# aa.net
KiCad netlist of a schematic drawn in EAGLE
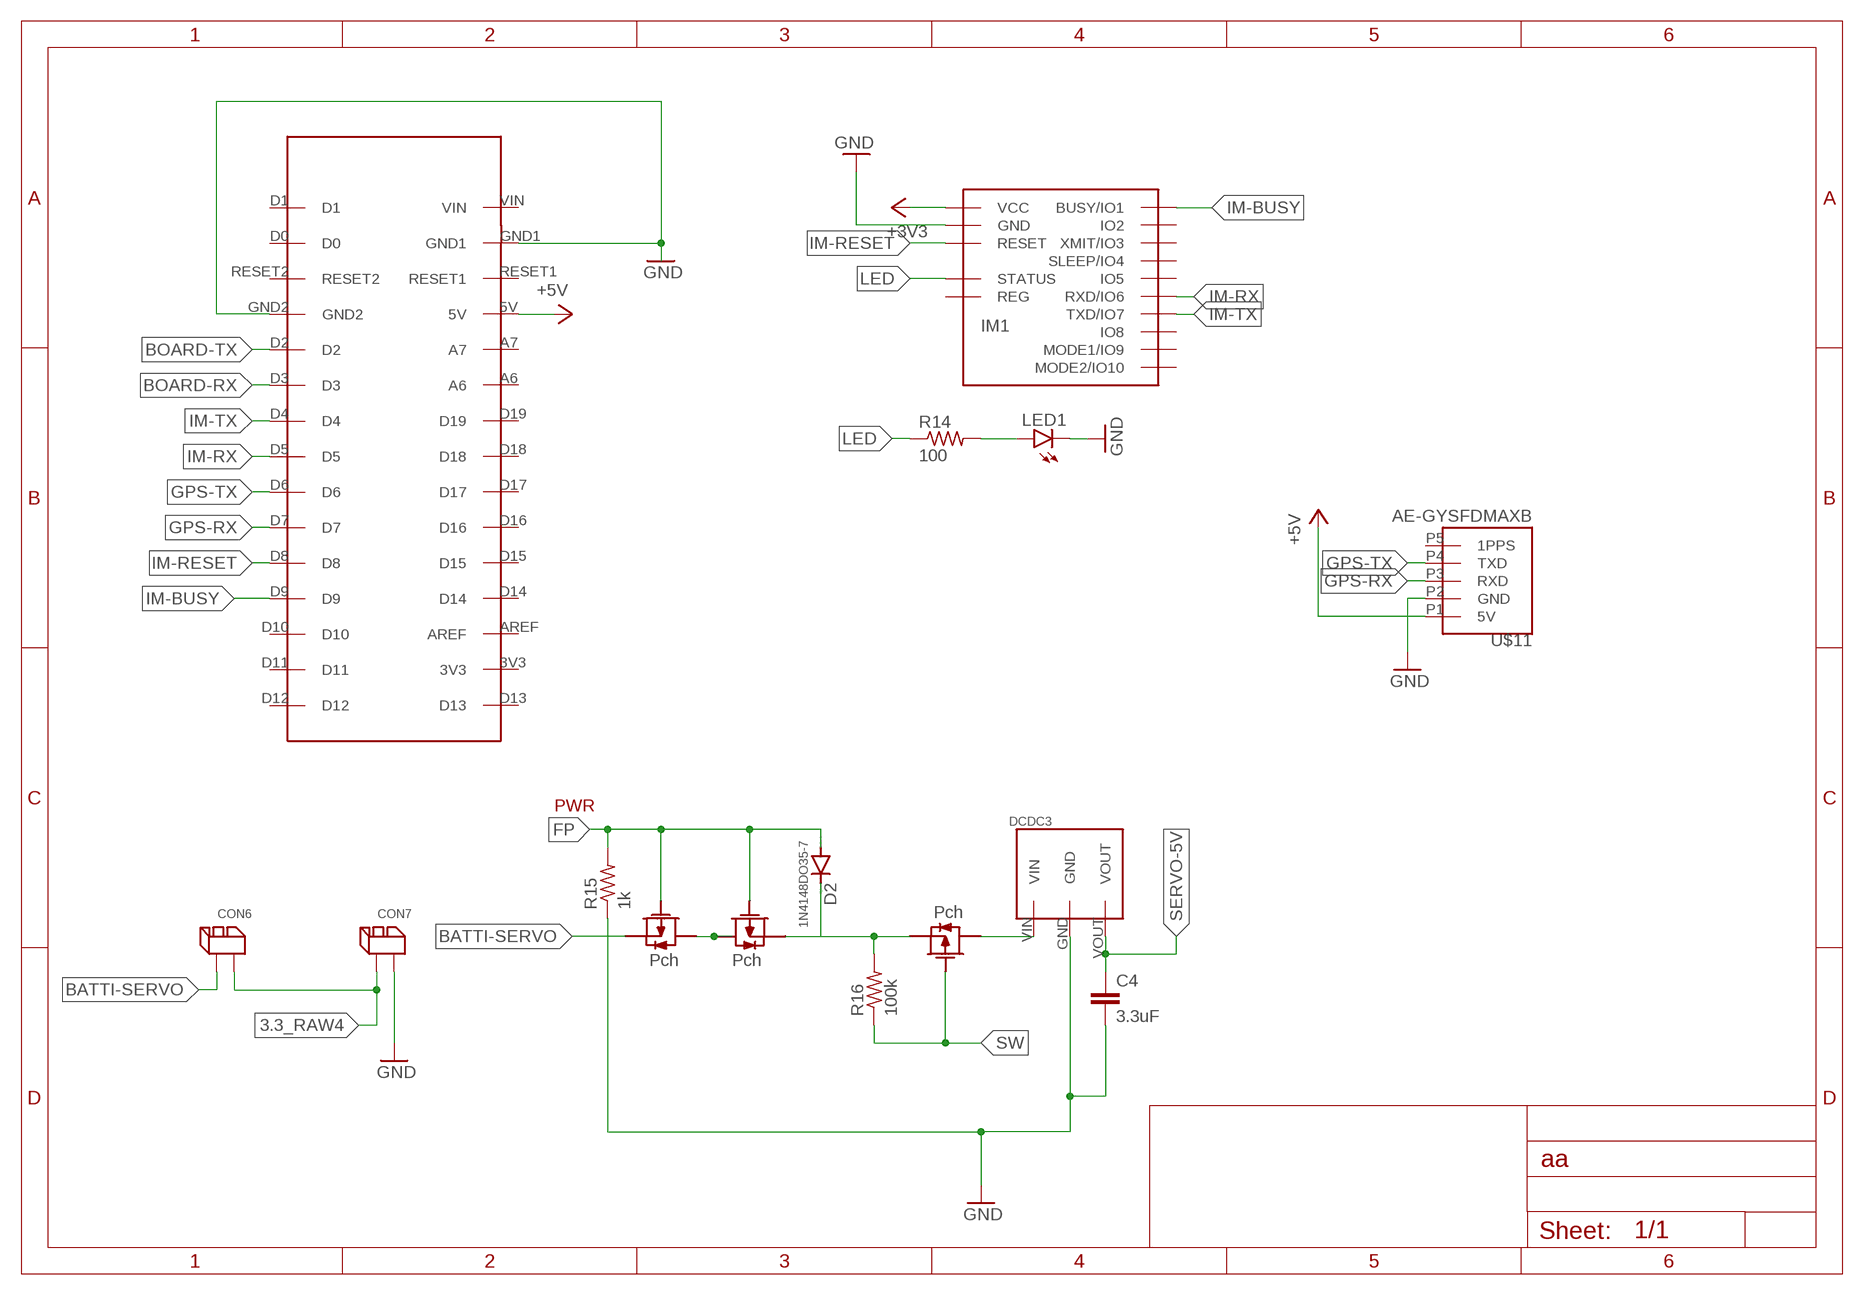
[diagram p0: schematic, sheet 1]

(export (version "E")
  (design (tool "Eeschema 10.0.6"))
  (components
    (comp (ref "C4")
      (value "3.3uF")
      (footprint "eagle-import:C025-024X044")
      (libsource (lib "eagle-import") (part "C-EU025-024X044"))
    )
    (comp (ref "CON6")
      (value "2PIN")
      (footprint "eagle-import:2PIN")
      (libsource (lib "eagle-import") (part "2PIN"))
    )
    (comp (ref "CON7")
      (value "2PIN")
      (footprint "eagle-import:2PIN")
      (libsource (lib "eagle-import") (part "2PIN"))
    )
    (comp (ref "D2")
      (value "1N4148DO35-7")
      (footprint "eagle-import:DO35-7")
      (libsource (lib "eagle-import") (part "1N4148DO35-7"))
    )
    (comp (ref "DCDC3")
      (value "5V1A_M78AR05-1")
      (footprint "eagle-import:5V1A_M78AR05-1")
      (libsource (lib "eagle-import") (part "5V1A_M78AR05-1"))
    )
    (comp (ref "IM1")
      (value "IM920_IM920C")
      (footprint "eagle-import:IM920_IM920C")
      (libsource (lib "eagle-import") (part "IM920_IM920C"))
    )
    (comp (ref "LED1")
      (value "LED5MM")
      (footprint "eagle-import:LED5MM")
      (libsource (lib "eagle-import") (part "LED5MM"))
    )
    (comp (ref "R14")
      (value "100")
      (footprint "eagle-import:0204_7")
      (libsource (lib "eagle-import") (part "R-US_0204/7"))
    )
    (comp (ref "R15")
      (value "1k")
      (footprint "eagle-import:0204_7")
      (libsource (lib "eagle-import") (part "R-US_0204/7"))
    )
    (comp (ref "R16")
      (value "100k")
      (footprint "eagle-import:0204_7")
      (libsource (lib "eagle-import") (part "R-US_0204/7"))
    )
    (comp (ref "U$7")
      (value "ARDUINONANO")
      (footprint "eagle-import:ARDUINONANO")
      (libsource (lib "eagle-import") (part "ARDUINONANO"))
    )
    (comp (ref "U$8")
      (value "2SJ681-PCH")
      (footprint "eagle-import:2SJ681")
      (libsource (lib "eagle-import") (part "2SJ681-PCH"))
    )
    (comp (ref "U$9")
      (value "2SJ681-PCH")
      (footprint "eagle-import:2SJ681")
      (libsource (lib "eagle-import") (part "2SJ681-PCH"))
    )
    (comp (ref "U$10")
      (value "2SJ681-PCH")
      (footprint "eagle-import:2SJ681")
      (libsource (lib "eagle-import") (part "2SJ681-PCH"))
    )
    (comp (ref "U$11")
      (value "AE-GYSFDMAXB")
      (footprint "eagle-import:AE-GYSFDMAXB")
      (libsource (lib "eagle-import") (part "AE-GYSFDMAXB"))
    )
  )
  (nets
    (net (code "1") (name "+3V3") (class "Default")
      (node (ref "IM1") (pin "$P17") (pinfunction "VCC_$P17") (pintype "bidirectional"))
    )
    (net (code "2") (name "+5V") (class "Default")
      (node (ref "U$11") (pin "P1") (pinfunction "5V_P1") (pintype "bidirectional"))
      (node (ref "U$7") (pin "5V") (pinfunction "5V_5V") (pintype "bidirectional"))
    )
    (net (code "3") (name "3.3_RAW4") (class "Default")
      (node (ref "CON6") (pin "P$1") (pinfunction "P$1_P$1") (pintype "bidirectional"))
      (node (ref "CON7") (pin "P$2") (pinfunction "P$2_P$2") (pintype "bidirectional"))
    )
    (net (code "4") (name "BATTI-SERVO") (class "Default")
      (node (ref "CON6") (pin "P$2") (pinfunction "P$2_P$2") (pintype "bidirectional"))
      (node (ref "U$8") (pin "SOURCE") (pinfunction "SOURCE_SOURCE") (pintype "bidirectional"))
    )
    (net (code "5") (name "BOARD-RX") (class "Default")
      (node (ref "U$7") (pin "D3") (pinfunction "D3_D3") (pintype "bidirectional"))
    )
    (net (code "6") (name "BOARD-TX") (class "Default")
      (node (ref "U$7") (pin "D2") (pinfunction "D2_D2") (pintype "bidirectional"))
    )
    (net (code "7") (name "FP") (class "Default")
      (node (ref "D2") (pin "A") (pinfunction "A_A") (pintype "passive"))
      (node (ref "R15") (pin "2") (pinfunction "2_2") (pintype "passive"))
      (node (ref "U$10") (pin "GATE") (pinfunction "GATE_GATE") (pintype "bidirectional"))
      (node (ref "U$8") (pin "GATE") (pinfunction "GATE_GATE") (pintype "bidirectional"))
    )
    (net (code "8") (name "GND") (class "Default")
      (node (ref "C4") (pin "2") (pinfunction "2_2") (pintype "passive"))
      (node (ref "CON7") (pin "P$1") (pinfunction "P$1_P$1") (pintype "bidirectional"))
      (node (ref "DCDC3") (pin "GND") (pinfunction "GND_GND") (pintype "bidirectional"))
      (node (ref "IM1") (pin "$P18") (pinfunction "GND_$P18") (pintype "bidirectional"))
      (node (ref "LED1") (pin "K") (pinfunction "C_K") (pintype "passive"))
      (node (ref "R15") (pin "1") (pinfunction "1_1") (pintype "passive"))
      (node (ref "U$11") (pin "P2") (pinfunction "GND_P2") (pintype "bidirectional"))
      (node (ref "U$7") (pin "GND1") (pinfunction "GND1_GND1") (pintype "bidirectional"))
      (node (ref "U$7") (pin "GND2") (pinfunction "GND2_GND2") (pintype "bidirectional"))
    )
    (net (code "9") (name "GPS-RX") (class "Default")
      (node (ref "U$11") (pin "P3") (pinfunction "RXD_P3") (pintype "bidirectional"))
      (node (ref "U$7") (pin "D7") (pinfunction "D7_D7") (pintype "bidirectional"))
    )
    (net (code "10") (name "GPS-TX") (class "Default")
      (node (ref "U$11") (pin "P4") (pinfunction "TXD_P4") (pintype "bidirectional"))
      (node (ref "U$7") (pin "D6") (pinfunction "D6_D6") (pintype "bidirectional"))
    )
    (net (code "11") (name "IM-BUSY") (class "Default")
      (node (ref "IM1") (pin "$P1") (pinfunction "BUSY/IO1_$P1") (pintype "bidirectional"))
      (node (ref "U$7") (pin "D9") (pinfunction "D9_D9") (pintype "bidirectional"))
    )
    (net (code "12") (name "IM-RESET") (class "Default")
      (node (ref "IM1") (pin "$P19") (pinfunction "RESET_$P19") (pintype "bidirectional"))
      (node (ref "U$7") (pin "D8") (pinfunction "D8_D8") (pintype "bidirectional"))
    )
    (net (code "13") (name "IM-RX") (class "Default")
      (node (ref "IM1") (pin "$P6") (pinfunction "RXD/IO6_$P6") (pintype "bidirectional"))
      (node (ref "U$7") (pin "D5") (pinfunction "D5_D5") (pintype "bidirectional"))
    )
    (net (code "14") (name "IM-TX") (class "Default")
      (node (ref "IM1") (pin "$P7") (pinfunction "TXD/IO7_$P7") (pintype "bidirectional"))
      (node (ref "U$7") (pin "D4") (pinfunction "D4_D4") (pintype "bidirectional"))
    )
    (net (code "15") (name "LED") (class "Default")
      (node (ref "IM1") (pin "$P15") (pinfunction "STATUS_$P15") (pintype "bidirectional"))
      (node (ref "R14") (pin "1") (pinfunction "1_1") (pintype "passive"))
    )
    (net (code "16") (name "Net-(D2-PadC)") (class "Default")
      (node (ref "D2") (pin "C") (pinfunction "C_C") (pintype "passive"))
      (node (ref "R16") (pin "2") (pinfunction "2_2") (pintype "passive"))
      (node (ref "U$10") (pin "SOURCE") (pinfunction "SOURCE_SOURCE") (pintype "bidirectional"))
      (node (ref "U$9") (pin "SOURCE") (pinfunction "SOURCE_SOURCE") (pintype "bidirectional"))
    )
    (net (code "17") (name "Net-(DCDC3-PadVIN)") (class "Default")
      (node (ref "DCDC3") (pin "VIN") (pinfunction "VIN_VIN") (pintype "bidirectional"))
      (node (ref "U$9") (pin "DRAIN") (pinfunction "DRAIN_DRAIN") (pintype "bidirectional"))
    )
    (net (code "18") (name "Net-(LED1-PadA)") (class "Default")
      (node (ref "LED1") (pin "A") (pinfunction "A_A") (pintype "passive"))
      (node (ref "R14") (pin "2") (pinfunction "2_2") (pintype "passive"))
    )
    (net (code "19") (name "Net-(U$10-PadDRAIN)") (class "Default")
      (node (ref "U$10") (pin "DRAIN") (pinfunction "DRAIN_DRAIN") (pintype "bidirectional"))
      (node (ref "U$8") (pin "DRAIN") (pinfunction "DRAIN_DRAIN") (pintype "bidirectional"))
    )
    (net (code "20") (name "SERVO-5V") (class "Default")
      (node (ref "C4") (pin "1") (pinfunction "1_1") (pintype "passive"))
      (node (ref "DCDC3") (pin "VOUT") (pinfunction "VOUT_VOUT") (pintype "bidirectional"))
    )
    (net (code "21") (name "SW") (class "Default")
      (node (ref "R16") (pin "1") (pinfunction "1_1") (pintype "passive"))
      (node (ref "U$9") (pin "GATE") (pinfunction "GATE_GATE") (pintype "bidirectional"))
    )
    (net (code "22") (name "unconnected-(IM1-IO2-Pad$P2)") (class "Default")
      (node (ref "IM1") (pin "$P2") (pinfunction "IO2_$P2") (pintype "bidirectional"))
    )
    (net (code "23") (name "unconnected-(IM1-IO5-Pad$P5)") (class "Default")
      (node (ref "IM1") (pin "$P5") (pinfunction "IO5_$P5") (pintype "bidirectional"))
    )
    (net (code "24") (name "unconnected-(IM1-IO8-Pad$P8)") (class "Default")
      (node (ref "IM1") (pin "$P8") (pinfunction "IO8_$P8") (pintype "bidirectional"))
    )
    (net (code "25") (name "unconnected-(IM1-MODE1{slash}IO9-Pad$P9)") (class "Default")
      (node (ref "IM1") (pin "$P9") (pinfunction "MODE1/IO9_$P9") (pintype "bidirectional"))
    )
    (net (code "26") (name "unconnected-(IM1-MODE2{slash}IO10-Pad$P10)") (class "Default")
      (node (ref "IM1") (pin "$P10") (pinfunction "MODE2/IO10_$P10") (pintype "bidirectional"))
    )
    (net (code "27") (name "unconnected-(IM1-REG-Pad$P16)") (class "Default")
      (node (ref "IM1") (pin "$P16") (pinfunction "REG_$P16") (pintype "bidirectional"))
    )
    (net (code "28") (name "unconnected-(IM1-SLEEP{slash}IO4-Pad$P4)") (class "Default")
      (node (ref "IM1") (pin "$P4") (pinfunction "SLEEP/IO4_$P4") (pintype "bidirectional"))
    )
    (net (code "29") (name "unconnected-(IM1-XMIT{slash}IO3-Pad$P3)") (class "Default")
      (node (ref "IM1") (pin "$P3") (pinfunction "XMIT/IO3_$P3") (pintype "bidirectional"))
    )
    (net (code "30") (name "unconnected-(U$7-Pad3V3)") (class "Default")
      (node (ref "U$7") (pin "3V3") (pinfunction "3V3_3V3") (pintype "bidirectional"))
    )
    (net (code "31") (name "unconnected-(U$7-PadA6)") (class "Default")
      (node (ref "U$7") (pin "A6") (pinfunction "A6_A6") (pintype "bidirectional"))
    )
    (net (code "32") (name "unconnected-(U$7-PadA7)") (class "Default")
      (node (ref "U$7") (pin "A7") (pinfunction "A7_A7") (pintype "bidirectional"))
    )
    (net (code "33") (name "unconnected-(U$7-PadAREF)") (class "Default")
      (node (ref "U$7") (pin "AREF") (pinfunction "AREF_AREF") (pintype "bidirectional"))
    )
    (net (code "34") (name "unconnected-(U$7-PadD0)") (class "Default")
      (node (ref "U$7") (pin "D0") (pinfunction "D0_D0") (pintype "bidirectional"))
    )
    (net (code "35") (name "unconnected-(U$7-PadD1)") (class "Default")
      (node (ref "U$7") (pin "D1") (pinfunction "D1_D1") (pintype "bidirectional"))
    )
    (net (code "36") (name "unconnected-(U$7-PadD10)") (class "Default")
      (node (ref "U$7") (pin "D10") (pinfunction "D10_D10") (pintype "bidirectional"))
    )
    (net (code "37") (name "unconnected-(U$7-PadD11)") (class "Default")
      (node (ref "U$7") (pin "D11") (pinfunction "D11_D11") (pintype "bidirectional"))
    )
    (net (code "38") (name "unconnected-(U$7-PadD12)") (class "Default")
      (node (ref "U$7") (pin "D12") (pinfunction "D12_D12") (pintype "bidirectional"))
    )
    (net (code "39") (name "unconnected-(U$7-PadD13)") (class "Default")
      (node (ref "U$7") (pin "D13") (pinfunction "D13_D13") (pintype "bidirectional"))
    )
    (net (code "40") (name "unconnected-(U$7-PadD14)") (class "Default")
      (node (ref "U$7") (pin "D14") (pinfunction "D14_D14") (pintype "bidirectional"))
    )
    (net (code "41") (name "unconnected-(U$7-PadD15)") (class "Default")
      (node (ref "U$7") (pin "D15") (pinfunction "D15_D15") (pintype "bidirectional"))
    )
    (net (code "42") (name "unconnected-(U$7-PadD16)") (class "Default")
      (node (ref "U$7") (pin "D16") (pinfunction "D16_D16") (pintype "bidirectional"))
    )
    (net (code "43") (name "unconnected-(U$7-PadD17)") (class "Default")
      (node (ref "U$7") (pin "D17") (pinfunction "D17_D17") (pintype "bidirectional"))
    )
    (net (code "44") (name "unconnected-(U$7-PadD18)") (class "Default")
      (node (ref "U$7") (pin "D18") (pinfunction "D18_D18") (pintype "bidirectional"))
    )
    (net (code "45") (name "unconnected-(U$7-PadD19)") (class "Default")
      (node (ref "U$7") (pin "D19") (pinfunction "D19_D19") (pintype "bidirectional"))
    )
    (net (code "46") (name "unconnected-(U$7-PadRESET1)") (class "Default")
      (node (ref "U$7") (pin "RESET1") (pinfunction "RESET1_RESET1") (pintype "bidirectional"))
    )
    (net (code "47") (name "unconnected-(U$7-PadRESET2)") (class "Default")
      (node (ref "U$7") (pin "RESET2") (pinfunction "RESET2_RESET2") (pintype "bidirectional"))
    )
    (net (code "48") (name "unconnected-(U$7-PadVIN)") (class "Default")
      (node (ref "U$7") (pin "VIN") (pinfunction "VIN_VIN") (pintype "bidirectional"))
    )
    (net (code "49") (name "unconnected-(U$11-1PPS-PadP5)") (class "Default")
      (node (ref "U$11") (pin "P5") (pinfunction "1PPS_P5") (pintype "bidirectional"))
    )
  )
)
